# Instrumentation_amplifier_CC2640R2.net
KiCad netlist of a schematic drawn in EAGLE
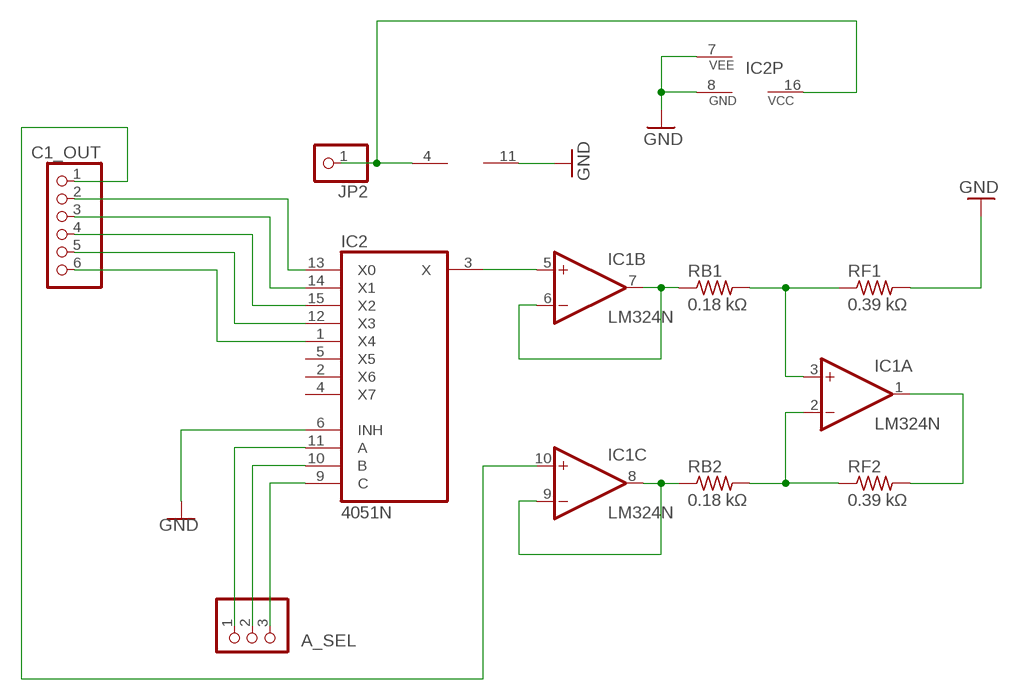
[diagram p0: schematic, sheet 1]

(export (version "E")
  (design (tool "Eeschema 10.0.6"))
  (components
    (comp (ref "A_SEL")
      (value "PINHD-1X3")
      (footprint "eagle-import:1X03")
      (libsource (lib "eagle-import") (part "PINHD-1X3"))
    )
    (comp (ref "C1_OUT")
      (value "PINHD-1X6")
      (footprint "eagle-import:1X06")
      (libsource (lib "eagle-import") (part "PINHD-1X6"))
    )
    (comp (ref "IC1")
      (value "LM324N")
      (footprint "eagle-import:DIL14")
      (libsource (lib "eagle-import") (part "LM324N"))
    )
    (comp (ref "IC2")
      (value "4051N")
      (footprint "eagle-import:DIL16")
      (libsource (lib "eagle-import") (part "4051N"))
    )
    (comp (ref "JP2")
      (value "PINHD-1X1")
      (footprint "eagle-import:1X01")
      (libsource (lib "eagle-import") (part "PINHD-1X1"))
    )
    (comp (ref "RB1")
      (value "0.18 kΩ")
      (footprint "eagle-import:0204_7")
      (libsource (lib "eagle-import") (part "R-US_0204/7"))
    )
    (comp (ref "RB2")
      (value "0.18 kΩ")
      (footprint "eagle-import:0204_7")
      (libsource (lib "eagle-import") (part "R-US_0204/7"))
    )
    (comp (ref "RF1")
      (value "0.39 kΩ")
      (footprint "eagle-import:0204_7")
      (libsource (lib "eagle-import") (part "R-US_0204/7"))
    )
    (comp (ref "RF2")
      (value "0.39 kΩ")
      (footprint "eagle-import:0204_7")
      (libsource (lib "eagle-import") (part "R-US_0204/7"))
    )
  )
  (nets
    (net (code "1") (name "GND") (class "Default")
      (node (ref "IC1") (pin "11") (pinfunction "V-_11") (pintype "power_in"))
      (node (ref "IC2") (pin "6") (pinfunction "INH_6") (pintype "input"))
      (node (ref "IC2") (pin "7") (pinfunction "VEE_7") (pintype "power_in"))
      (node (ref "IC2") (pin "8") (pinfunction "GND_8") (pintype "power_in"))
      (node (ref "RF1") (pin "2") (pinfunction "2_2") (pintype "passive"))
    )
    (net (code "2") (name "Net-(IC1A-+IN)") (class "Default")
      (node (ref "IC1") (pin "3") (pinfunction "+IN_3") (pintype "input"))
      (node (ref "RB1") (pin "2") (pinfunction "2_2") (pintype "passive"))
      (node (ref "RF1") (pin "1") (pinfunction "1_1") (pintype "passive"))
    )
    (net (code "3") (name "Net-(IC1A--IN)") (class "Default")
      (node (ref "IC1") (pin "2") (pinfunction "-IN_2") (pintype "input"))
      (node (ref "RB2") (pin "2") (pinfunction "2_2") (pintype "passive"))
      (node (ref "RF2") (pin "1") (pinfunction "1_1") (pintype "passive"))
    )
    (net (code "4") (name "Net-(IC1A-OUT)") (class "Default")
      (node (ref "IC1") (pin "1") (pinfunction "OUT_1") (pintype "output"))
      (node (ref "RF2") (pin "2") (pinfunction "2_2") (pintype "passive"))
    )
    (net (code "5") (name "Net-(IC1B-+IN)") (class "Default")
      (node (ref "IC1") (pin "5") (pinfunction "+IN_5") (pintype "input"))
      (node (ref "IC2") (pin "3") (pinfunction "X_3") (pintype "bidirectional"))
    )
    (net (code "6") (name "Net-(IC1B--IN)") (class "Default")
      (node (ref "IC1") (pin "6") (pinfunction "-IN_6") (pintype "input"))
      (node (ref "IC1") (pin "7") (pinfunction "OUT_7") (pintype "output"))
      (node (ref "RB1") (pin "1") (pinfunction "1_1") (pintype "passive"))
    )
    (net (code "7") (name "Net-(IC1C-+IN)") (class "Default")
      (node (ref "C1_OUT") (pin "1") (pinfunction "1_1") (pintype "passive"))
      (node (ref "IC1") (pin "10") (pinfunction "+IN_10") (pintype "input"))
    )
    (net (code "8") (name "Net-(IC1C--IN)") (class "Default")
      (node (ref "IC1") (pin "8") (pinfunction "OUT_8") (pintype "output"))
      (node (ref "IC1") (pin "9") (pinfunction "-IN_9") (pintype "input"))
      (node (ref "RB2") (pin "1") (pinfunction "1_1") (pintype "passive"))
    )
    (net (code "9") (name "Net-(IC1E-V+)") (class "Default")
      (node (ref "IC1") (pin "4") (pinfunction "V+_4") (pintype "power_in"))
      (node (ref "IC2") (pin "16") (pinfunction "VCC_16") (pintype "power_in"))
      (node (ref "JP2") (pin "1") (pinfunction "1_1") (pintype "passive"))
    )
    (net (code "10") (name "Net-(IC2A-A)") (class "Default")
      (node (ref "A_SEL") (pin "1") (pinfunction "1_1") (pintype "passive"))
      (node (ref "IC2") (pin "11") (pinfunction "A_11") (pintype "input"))
    )
    (net (code "11") (name "Net-(IC2A-B)") (class "Default")
      (node (ref "A_SEL") (pin "2") (pinfunction "2_2") (pintype "passive"))
      (node (ref "IC2") (pin "10") (pinfunction "B_10") (pintype "input"))
    )
    (net (code "12") (name "Net-(IC2A-C)") (class "Default")
      (node (ref "A_SEL") (pin "3") (pinfunction "3_3") (pintype "passive"))
      (node (ref "IC2") (pin "9") (pinfunction "C_9") (pintype "input"))
    )
    (net (code "13") (name "Net-(IC2A-X0)") (class "Default")
      (node (ref "C1_OUT") (pin "2") (pinfunction "2_2") (pintype "passive"))
      (node (ref "IC2") (pin "13") (pinfunction "X0_13") (pintype "bidirectional"))
    )
    (net (code "14") (name "Net-(IC2A-X1)") (class "Default")
      (node (ref "C1_OUT") (pin "3") (pinfunction "3_3") (pintype "passive"))
      (node (ref "IC2") (pin "14") (pinfunction "X1_14") (pintype "bidirectional"))
    )
    (net (code "15") (name "Net-(IC2A-X2)") (class "Default")
      (node (ref "C1_OUT") (pin "4") (pinfunction "4_4") (pintype "passive"))
      (node (ref "IC2") (pin "15") (pinfunction "X2_15") (pintype "bidirectional"))
    )
    (net (code "16") (name "Net-(IC2A-X3)") (class "Default")
      (node (ref "C1_OUT") (pin "5") (pinfunction "5_5") (pintype "passive"))
      (node (ref "IC2") (pin "12") (pinfunction "X3_12") (pintype "bidirectional"))
    )
    (net (code "17") (name "Net-(IC2A-X4)") (class "Default")
      (node (ref "C1_OUT") (pin "6") (pinfunction "6_6") (pintype "passive"))
      (node (ref "IC2") (pin "1") (pinfunction "X4_1") (pintype "bidirectional"))
    )
    (net (code "18") (name "unconnected-(IC2A-X5-Pad5)") (class "Default")
      (node (ref "IC2") (pin "5") (pinfunction "X5_5") (pintype "bidirectional"))
    )
    (net (code "19") (name "unconnected-(IC2A-X6-Pad2)") (class "Default")
      (node (ref "IC2") (pin "2") (pinfunction "X6_2") (pintype "bidirectional"))
    )
    (net (code "20") (name "unconnected-(IC2A-X7-Pad4)") (class "Default")
      (node (ref "IC2") (pin "4") (pinfunction "X7_4") (pintype "bidirectional"))
    )
  )
)
